# design.net
KiCad netlist of a schematic drawn in Altium Designer
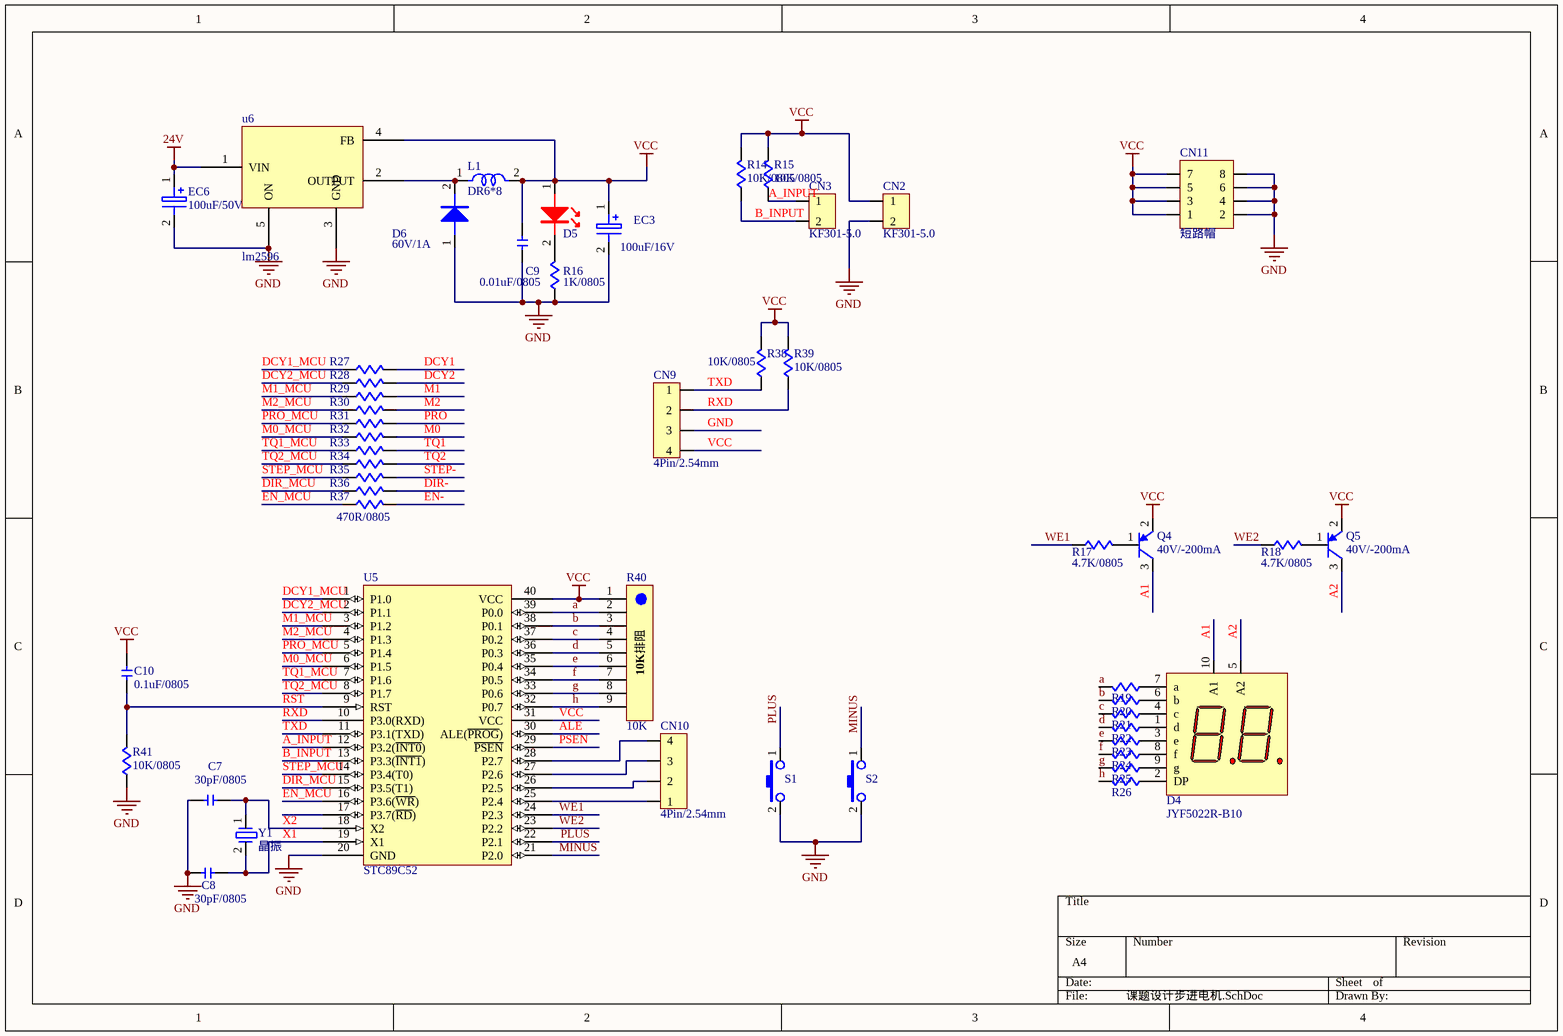
[diagram p0: 课题设计步进电机.SchDoc]

(export (version "E")
  (design (tool "Eeschema 10.0.6"))
  (components
    (comp (ref "C7")
      (value "30pF/0805")
      (footprint "WSC0805")
      (description "R21080010/工业C/消费C/贴片电容/30pF±5%/50V/NPO/0805")
      (libsource (lib "Capacitor_21") (part "R21080010"))
    )
    (comp (ref "C8")
      (value "30pF/0805")
      (footprint "WSC0805")
      (description "R21080010/工业C/消费C/贴片电容/30pF±5%/50V/NPO/0805")
      (libsource (lib "Capacitor_21") (part "R21080010"))
    )
    (comp (ref "C9")
      (value "0.01uF/0805")
      (footprint "WSC0805")
      (description "R21050097/工业C/消费C/贴片电容/0.01uF±5%/50V/NPO/0805")
      (libsource (lib "Capacitor_21") (part "R21050097"))
    )
    (comp (ref "C10")
      (value "0.1uF/0805")
      (footprint "WSC0805")
      (description "R21050005/工业B/消费B/贴片电容/0.1uF±10%/50V/X7R/0805")
      (libsource (lib "Capacitor_21") (part "R21050005"))
    )
    (comp (ref "CN2")
      (value "KF301-5.0")
      (footprint "KF301-5.0")
      (libsource (lib "Integrated_Library1") (part "KF301-5.0"))
    )
    (comp (ref "CN3")
      (value "KF301-5.0")
      (footprint "KF301-5.0")
      (libsource (lib "Integrated_Library1") (part "KF301-5.0"))
    )
    (comp (ref "CN9")
      (value "4Pin/2.54mm")
      (footprint "THT-CON4-2.54-2.54A/S-H8.5")
      (description "R30041122/消费B/普通插座/单排排母/4PIN/3A/单排/直脚/鱼叉母座/2.54mm/-40~105℃/H=8.5mm")
      (libsource (lib "Connector_30") (part "R30041122"))
    )
    (comp (ref "CN10")
      (value "4Pin/2.54mm")
      (footprint "THT-CON4-2.54-2.54A/S-H8.5")
      (description "R30041122/消费B/普通插座/单排排母/4PIN/3A/单排/直脚/鱼叉母座/2.54mm/-40~105℃/H=8.5mm")
      (libsource (lib "") (part "R30041122_1"))
    )
    (comp (ref "CN11")
      (value "短路帽")
      (footprint "THT-CON2*4-2.54-5.08A/D")
      (libsource (lib "temp") (part "2*54Pin/2.54mm"))
    )
    (comp (ref "D4")
      (value "JYF5022R-B10")
      (footprint "LED10-2.54*15.24-19A/S-AA")
      (description "R26010188/消费C/数码管/2位/共阳/红色630nm/40mcd/25*19*8mm/无铅")
      (libsource (lib "Semiconductor_26") (part "R26010188"))
    )
    (comp (ref "D5")
      (value "LED0805")
      (footprint "SD0805")
      (description "R26010108/工业A/消费A/发光二极管/红色/61mcd@20mA/0805SMD/LED0805")
      (libsource (lib "Semiconductor_26") (part "R26010108"))
    )
    (comp (ref "D6")
      (value "60V/1A")
      (footprint "SDO-214AC(SMA)")
      (description "R26030097/工业C/肖特基二极管/60V/1A/0.70V/SMA/B160")
      (libsource (lib "Semiconductor_26") (part "R26030097"))
    )
    (comp (ref "EC3")
      (value "100uF/16V")
      (footprint "CAPC2-5-5*11A/D")
      (description "R21010764/消费C/铝电解电容/105℃/100uF/16V/φ5*11")
      (libsource (lib "Capacitor_21") (part "R21010764"))
    )
    (comp (ref "EC6")
      (value "100uF/50V")
      (footprint "CAPC2-3.5-8*11.5A/S")
      (description "R21010695/消费C/电解电容/105℃/100uF/50v/φ8*11.5/引脚间距3.5mm")
      (libsource (lib "Capacitor_21") (part "R21010695"))
    )
    (comp (ref "L1")
      (value "DR6*8")
      (footprint "L2-3-8*11A/S")
      (description "R22011019/消费A/工字型电感DR6*8/100uH/MC1600-L3")
      (libsource (lib "Inductor_22") (part "R22011019"))
    )
    (comp (ref "Q4")
      (value "40V/-200mA")
      (footprint "WSOT-23")
      (description "R26080002/工业A/消费A/小信号三极管/PNP/-40V/-200mA/SOT-23")
      (libsource (lib "Semiconductor_26") (part "R26080002"))
    )
    (comp (ref "Q5")
      (value "40V/-200mA")
      (footprint "WSOT-23")
      (description "R26080002/工业A/消费A/小信号三极管/PNP/-40V/-200mA/SOT-23")
      (libsource (lib "Semiconductor_26") (part "R26080002"))
    )
    (comp (ref "R14")
      (value "10K/0805")
      (footprint "WSR0805")
      (description "R20180048/工业A/消费A/贴片电阻/1/8W/10KΩ±5%/0805")
      (libsource (lib "Resistor_20") (part "R20180048"))
    )
    (comp (ref "R15")
      (value "10K/0805")
      (footprint "WSR0805")
      (description "R20180048/工业A/消费A/贴片电阻/1/8W/10KΩ±5%/0805")
      (libsource (lib "Resistor_20") (part "R20180048"))
    )
    (comp (ref "R16")
      (value "1K/0805")
      (footprint "WSR0805")
      (description "R20180023/工业A/消费A/贴片电阻/1/8W/1KΩ±5%/0805")
      (libsource (lib "Resistor_20") (part "R20180023"))
    )
    (comp (ref "R17")
      (value "4.7K/0805")
      (footprint "WSR0805")
      (description "R20180039/工业A/消费A/贴片电阻/1/8W/4.7KΩ±5%/0805")
      (libsource (lib "Resistor_20") (part "R20180039"))
    )
    (comp (ref "R18")
      (value "4.7K/0805")
      (footprint "WSR0805")
      (description "R20180039/工业A/消费A/贴片电阻/1/8W/4.7KΩ±5%/0805")
      (libsource (lib "Resistor_20") (part "R20180039"))
    )
    (comp (ref "R19")
      (value "470R/0805")
      (footprint "WSR0805")
      (description "R20180017/工业A/消费A/贴片电阻/1/8W/470Ω±5%/0805")
      (libsource (lib "Resistor_20") (part "R20180017"))
    )
    (comp (ref "R20")
      (value "470R/0805")
      (footprint "WSR0805")
      (description "R20180017/工业A/消费A/贴片电阻/1/8W/470Ω±5%/0805")
      (libsource (lib "Resistor_20") (part "R20180017"))
    )
    (comp (ref "R21")
      (value "470R/0805")
      (footprint "WSR0805")
      (description "R20180017/工业A/消费A/贴片电阻/1/8W/470Ω±5%/0805")
      (libsource (lib "Resistor_20") (part "R20180017"))
    )
    (comp (ref "R22")
      (value "470R/0805")
      (footprint "WSR0805")
      (description "R20180017/工业A/消费A/贴片电阻/1/8W/470Ω±5%/0805")
      (libsource (lib "Resistor_20") (part "R20180017"))
    )
    (comp (ref "R23")
      (value "470R/0805")
      (footprint "WSR0805")
      (description "R20180017/工业A/消费A/贴片电阻/1/8W/470Ω±5%/0805")
      (libsource (lib "Resistor_20") (part "R20180017"))
    )
    (comp (ref "R24")
      (value "470R/0805")
      (footprint "WSR0805")
      (description "R20180017/工业A/消费A/贴片电阻/1/8W/470Ω±5%/0805")
      (libsource (lib "Resistor_20") (part "R20180017"))
    )
    (comp (ref "R25")
      (value "470R/0805")
      (footprint "WSR0805")
      (description "R20180017/工业A/消费A/贴片电阻/1/8W/470Ω±5%/0805")
      (libsource (lib "Resistor_20") (part "R20180017"))
    )
    (comp (ref "R26")
      (value "470R/0805")
      (footprint "WSR0805")
      (description "R20180017/工业A/消费A/贴片电阻/1/8W/470Ω±5%/0805")
      (libsource (lib "Resistor_20") (part "R20180017"))
    )
    (comp (ref "R27")
      (value "470R/0805")
      (footprint "WSR0805")
      (description "R20180245/工业C/消费C/贴片电阻/1/8W/470Ω±1%/0805/ROHS")
      (libsource (lib "Resistor_20") (part "R20180245"))
    )
    (comp (ref "R28")
      (value "470R/0805")
      (footprint "WSR0805")
      (description "R20180245/工业C/消费C/贴片电阻/1/8W/470Ω±1%/0805/ROHS")
      (libsource (lib "Resistor_20") (part "R20180245"))
    )
    (comp (ref "R29")
      (value "470R/0805")
      (footprint "WSR0805")
      (description "R20180245/工业C/消费C/贴片电阻/1/8W/470Ω±1%/0805/ROHS")
      (libsource (lib "Resistor_20") (part "R20180245"))
    )
    (comp (ref "R30")
      (value "470R/0805")
      (footprint "WSR0805")
      (description "R20180245/工业C/消费C/贴片电阻/1/8W/470Ω±1%/0805/ROHS")
      (libsource (lib "Resistor_20") (part "R20180245"))
    )
    (comp (ref "R31")
      (value "470R/0805")
      (footprint "WSR0805")
      (description "R20180245/工业C/消费C/贴片电阻/1/8W/470Ω±1%/0805/ROHS")
      (libsource (lib "Resistor_20") (part "R20180245"))
    )
    (comp (ref "R32")
      (value "470R/0805")
      (footprint "WSR0805")
      (description "R20180245/工业C/消费C/贴片电阻/1/8W/470Ω±1%/0805/ROHS")
      (libsource (lib "Resistor_20") (part "R20180245"))
    )
    (comp (ref "R33")
      (value "470R/0805")
      (footprint "WSR0805")
      (description "R20180245/工业C/消费C/贴片电阻/1/8W/470Ω±1%/0805/ROHS")
      (libsource (lib "Resistor_20") (part "R20180245"))
    )
    (comp (ref "R34")
      (value "470R/0805")
      (footprint "WSR0805")
      (description "R20180245/工业C/消费C/贴片电阻/1/8W/470Ω±1%/0805/ROHS")
      (libsource (lib "Resistor_20") (part "R20180245"))
    )
    (comp (ref "R35")
      (value "470R/0805")
      (footprint "WSR0805")
      (description "R20180245/工业C/消费C/贴片电阻/1/8W/470Ω±1%/0805/ROHS")
      (libsource (lib "Resistor_20") (part "R20180245"))
    )
    (comp (ref "R36")
      (value "470R/0805")
      (footprint "WSR0805")
      (description "R20180245/工业C/消费C/贴片电阻/1/8W/470Ω±1%/0805/ROHS")
      (libsource (lib "Resistor_20") (part "R20180245"))
    )
    (comp (ref "R37")
      (value "470R/0805")
      (footprint "WSR0805")
      (description "R20180245/工业C/消费C/贴片电阻/1/8W/470Ω±1%/0805/ROHS")
      (libsource (lib "Resistor_20") (part "R20180245"))
    )
    (comp (ref "R38")
      (value "10K/0805")
      (footprint "WSR0805")
      (description "R20180048/工业A/消费A/贴片电阻/1/8W/10KΩ±5%/0805")
      (libsource (lib "Resistor_20") (part "R20180048"))
    )
    (comp (ref "R39")
      (value "10K/0805")
      (footprint "WSR0805")
      (description "R20180048/工业A/消费A/贴片电阻/1/8W/10KΩ±5%/0805")
      (libsource (lib "Resistor_20") (part "R20180048"))
    )
    (comp (ref "R40") (value "10K") (footprint "R_9*2.54") (libsource (lib "lib of tj") (part "插件排阻")))
    (comp (ref "R41")
      (value "10K/0805")
      (footprint "WSR0805")
      (description "R20180048/工业A/消费A/贴片电阻/1/8W/10KΩ±5%/0805")
      (libsource (lib "Resistor_20") (part "R20180048"))
    )
    (comp (ref "S1")
      (value "12VDC/30mA")
      (footprint "THT-SW4-6.5*4.5A/D")
      (description "R34010007/消费A/微动开关/12VDC/30mA/6*6*4.3mm/插件")
      (libsource (lib "Low-tension_34") (part "R34010007"))
    )
    (comp (ref "S2")
      (value "12VDC/30mA")
      (footprint "THT-SW4-6.5*4.5A/D")
      (description "R34010007/消费A/微动开关/12VDC/30mA/6*6*4.3mm/插件")
      (libsource (lib "Low-tension_34") (part "R34010007"))
    )
    (comp (ref "U5")
      (value "STC89C52")
      (footprint "DIP-40")
      (libsource (lib "Integrated_Library1") (part "AT89C51"))
    )
    (comp (ref "u6")
      (value "lm2596")
      (footprint "TO-220-5L")
      (libsource (lib "Integrated_Library1") (part "lm2596"))
    )
    (comp (ref "Y1") (value "晶振") (footprint "HC-49") (libsource (lib "temp") (part "晶振")))
  )
  (nets
    (net (code "1") (name "/A1") (class "Default")
      (node (ref "D4") (pin "10") (pinfunction "A1_10") (pintype "passive"))
      (node (ref "Q4") (pin "3") (pinfunction "C_3") (pintype "passive"))
    )
    (net (code "2") (name "/A2") (class "Default")
      (node (ref "D4") (pin "5") (pinfunction "A2_5") (pintype "passive"))
      (node (ref "Q5") (pin "3") (pinfunction "C_3") (pintype "passive"))
    )
    (net (code "3") (name "/ALE") (class "Default")
      (node (ref "U5") (pin "30") (pinfunction "ALE(~{PROG})_30") (pintype "bidirectional"))
    )
    (net (code "4") (name "/A_INPUT") (class "Default")
      (node (ref "CN3") (pin "1") (pinfunction "1_1") (pintype "passive"))
      (node (ref "R15") (pin "1") (pinfunction "1_1") (pintype "passive"))
      (node (ref "U5") (pin "12") (pinfunction "P3.2(~{INT0})_12") (pintype "bidirectional"))
    )
    (net (code "5") (name "/B_INPUT") (class "Default")
      (node (ref "CN3") (pin "2") (pinfunction "2_2") (pintype "passive"))
      (node (ref "R14") (pin "1") (pinfunction "1_1") (pintype "passive"))
      (node (ref "U5") (pin "13") (pinfunction "P3.3(~{INT1})_13") (pintype "bidirectional"))
    )
    (net (code "6") (name "/DCY1") (class "Default")
      (node (ref "R27") (pin "2") (pinfunction "2_2") (pintype "passive"))
    )
    (net (code "7") (name "/DCY1_MCU") (class "Default")
      (node (ref "R27") (pin "1") (pinfunction "1_1") (pintype "passive"))
      (node (ref "U5") (pin "1") (pinfunction "P1.0_1") (pintype "bidirectional"))
    )
    (net (code "8") (name "/DCY2") (class "Default")
      (node (ref "R28") (pin "2") (pinfunction "2_2") (pintype "passive"))
    )
    (net (code "9") (name "/DCY2_MCU") (class "Default")
      (node (ref "R28") (pin "1") (pinfunction "1_1") (pintype "passive"))
      (node (ref "U5") (pin "2") (pinfunction "P1.1_2") (pintype "bidirectional"))
    )
    (net (code "10") (name "/DIR-") (class "Default")
      (node (ref "R36") (pin "2") (pinfunction "2_2") (pintype "passive"))
    )
    (net (code "11") (name "/DIR_MCU") (class "Default")
      (node (ref "R36") (pin "1") (pinfunction "1_1") (pintype "passive"))
      (node (ref "U5") (pin "15") (pinfunction "P3.5(T1)_15") (pintype "bidirectional"))
    )
    (net (code "12") (name "/EN-") (class "Default")
      (node (ref "R37") (pin "2") (pinfunction "2_2") (pintype "passive"))
    )
    (net (code "13") (name "/EN_MCU") (class "Default")
      (node (ref "R37") (pin "1") (pinfunction "1_1") (pintype "passive"))
      (node (ref "U5") (pin "16") (pinfunction "P3.6(~{WR})_16") (pintype "bidirectional"))
    )
    (net (code "14") (name "/M0") (class "Default")
      (node (ref "R32") (pin "2") (pinfunction "2_2") (pintype "passive"))
    )
    (net (code "15") (name "/M0_MCU") (class "Default")
      (node (ref "R32") (pin "1") (pinfunction "1_1") (pintype "passive"))
      (node (ref "U5") (pin "6") (pinfunction "P1.5_6") (pintype "bidirectional"))
    )
    (net (code "16") (name "/M1") (class "Default")
      (node (ref "R29") (pin "2") (pinfunction "2_2") (pintype "passive"))
    )
    (net (code "17") (name "/M1_MCU") (class "Default")
      (node (ref "R29") (pin "1") (pinfunction "1_1") (pintype "passive"))
      (node (ref "U5") (pin "3") (pinfunction "P1.2_3") (pintype "bidirectional"))
    )
    (net (code "18") (name "/M2") (class "Default")
      (node (ref "R30") (pin "2") (pinfunction "2_2") (pintype "passive"))
    )
    (net (code "19") (name "/M2_MCU") (class "Default")
      (node (ref "R30") (pin "1") (pinfunction "1_1") (pintype "passive"))
      (node (ref "U5") (pin "4") (pinfunction "P1.3_4") (pintype "bidirectional"))
    )
    (net (code "20") (name "/MINUS") (class "Default")
      (node (ref "S2") (pin "1") (pinfunction "1_1") (pintype "passive"))
      (node (ref "U5") (pin "21") (pinfunction "P2.0_21") (pintype "bidirectional"))
    )
    (net (code "21") (name "/PLUS") (class "Default")
      (node (ref "S1") (pin "1") (pinfunction "1_1") (pintype "passive"))
      (node (ref "U5") (pin "22") (pinfunction "P2.1_22") (pintype "bidirectional"))
    )
    (net (code "22") (name "/PRO") (class "Default")
      (node (ref "R31") (pin "2") (pinfunction "2_2") (pintype "passive"))
    )
    (net (code "23") (name "/PRO_MCU") (class "Default")
      (node (ref "R31") (pin "1") (pinfunction "1_1") (pintype "passive"))
      (node (ref "U5") (pin "5") (pinfunction "P1.4_5") (pintype "bidirectional"))
    )
    (net (code "24") (name "/PSEN") (class "Default")
      (node (ref "U5") (pin "29") (pinfunction "~{PSEN}_29") (pintype "bidirectional"))
    )
    (net (code "25") (name "/RST") (class "Default")
      (node (ref "C10") (pin "1") (pinfunction "1_1") (pintype "passive"))
      (node (ref "R41") (pin "2") (pinfunction "2_2") (pintype "passive"))
      (node (ref "U5") (pin "9") (pinfunction "RST_9") (pintype "input"))
    )
    (net (code "26") (name "/RXD") (class "Default")
      (node (ref "CN9") (pin "2") (pinfunction "2_2") (pintype "passive"))
      (node (ref "R39") (pin "1") (pinfunction "1_1") (pintype "passive"))
      (node (ref "U5") (pin "10") (pinfunction "P3.0(RXD)_10") (pintype "passive"))
    )
    (net (code "27") (name "/STEP-") (class "Default")
      (node (ref "R35") (pin "2") (pinfunction "2_2") (pintype "passive"))
    )
    (net (code "28") (name "/STEP_MCU") (class "Default")
      (node (ref "R35") (pin "1") (pinfunction "1_1") (pintype "passive"))
      (node (ref "U5") (pin "14") (pinfunction "P3.4(T0)_14") (pintype "bidirectional"))
    )
    (net (code "29") (name "/TQ1") (class "Default")
      (node (ref "R33") (pin "2") (pinfunction "2_2") (pintype "passive"))
    )
    (net (code "30") (name "/TQ1_MCU") (class "Default")
      (node (ref "R33") (pin "1") (pinfunction "1_1") (pintype "passive"))
      (node (ref "U5") (pin "7") (pinfunction "P1.6_7") (pintype "bidirectional"))
    )
    (net (code "31") (name "/TQ2") (class "Default")
      (node (ref "R34") (pin "2") (pinfunction "2_2") (pintype "passive"))
    )
    (net (code "32") (name "/TQ2_MCU") (class "Default")
      (node (ref "R34") (pin "1") (pinfunction "1_1") (pintype "passive"))
      (node (ref "U5") (pin "8") (pinfunction "P1.7_8") (pintype "bidirectional"))
    )
    (net (code "33") (name "/TXD") (class "Default")
      (node (ref "CN9") (pin "1") (pinfunction "1_1") (pintype "passive"))
      (node (ref "R38") (pin "1") (pinfunction "1_1") (pintype "passive"))
      (node (ref "U5") (pin "11") (pinfunction "P3.1(TXD)_11") (pintype "bidirectional"))
    )
    (net (code "34") (name "/WE1") (class "Default")
      (node (ref "R17") (pin "1") (pinfunction "1_1") (pintype "passive"))
      (node (ref "U5") (pin "24") (pinfunction "P2.3_24") (pintype "bidirectional"))
    )
    (net (code "35") (name "/WE2") (class "Default")
      (node (ref "R18") (pin "1") (pinfunction "1_1") (pintype "passive"))
      (node (ref "U5") (pin "23") (pinfunction "P2.2_23") (pintype "bidirectional"))
    )
    (net (code "36") (name "/X1") (class "Default")
      (node (ref "C8") (pin "2") (pinfunction "2_2") (pintype "passive"))
      (node (ref "U5") (pin "19") (pinfunction "X1_19") (pintype "input"))
      (node (ref "Y1") (pin "2") (pinfunction "2_2") (pintype "passive"))
    )
    (net (code "37") (name "/X2") (class "Default")
      (node (ref "C7") (pin "2") (pinfunction "2_2") (pintype "passive"))
      (node (ref "U5") (pin "18") (pinfunction "X2_18") (pintype "input"))
      (node (ref "Y1") (pin "1") (pinfunction "1_1") (pintype "passive"))
    )
    (net (code "38") (name "/a") (class "Default")
      (node (ref "R19") (pin "2") (pinfunction "2_2") (pintype "passive"))
      (node (ref "R40") (pin "2") (pinfunction "2_2") (pintype "passive"))
      (node (ref "U5") (pin "39") (pinfunction "P0.0_39") (pintype "bidirectional"))
    )
    (net (code "39") (name "/b") (class "Default")
      (node (ref "R20") (pin "2") (pinfunction "2_2") (pintype "passive"))
      (node (ref "R40") (pin "3") (pinfunction "3_3") (pintype "passive"))
      (node (ref "U5") (pin "38") (pinfunction "P0.1_38") (pintype "bidirectional"))
    )
    (net (code "40") (name "/c") (class "Default")
      (node (ref "R21") (pin "2") (pinfunction "2_2") (pintype "passive"))
      (node (ref "R40") (pin "4") (pinfunction "4_4") (pintype "passive"))
      (node (ref "U5") (pin "37") (pinfunction "P0.2_37") (pintype "bidirectional"))
    )
    (net (code "41") (name "/d") (class "Default")
      (node (ref "R22") (pin "2") (pinfunction "2_2") (pintype "passive"))
      (node (ref "R40") (pin "5") (pinfunction "5_5") (pintype "passive"))
      (node (ref "U5") (pin "36") (pinfunction "P0.3_36") (pintype "bidirectional"))
    )
    (net (code "42") (name "/e") (class "Default")
      (node (ref "R23") (pin "2") (pinfunction "2_2") (pintype "passive"))
      (node (ref "R40") (pin "6") (pinfunction "6_6") (pintype "passive"))
      (node (ref "U5") (pin "35") (pinfunction "P0.4_35") (pintype "bidirectional"))
    )
    (net (code "43") (name "/f") (class "Default")
      (node (ref "R24") (pin "2") (pinfunction "2_2") (pintype "passive"))
      (node (ref "R40") (pin "7") (pinfunction "7_7") (pintype "passive"))
      (node (ref "U5") (pin "34") (pinfunction "P0.5_34") (pintype "bidirectional"))
    )
    (net (code "44") (name "/g") (class "Default")
      (node (ref "R25") (pin "2") (pinfunction "2_2") (pintype "passive"))
      (node (ref "R40") (pin "8") (pinfunction "8_8") (pintype "passive"))
      (node (ref "U5") (pin "33") (pinfunction "P0.6_33") (pintype "bidirectional"))
    )
    (net (code "45") (name "/h") (class "Default")
      (node (ref "R26") (pin "2") (pinfunction "2_2") (pintype "passive"))
      (node (ref "R40") (pin "9") (pinfunction "9_9") (pintype "passive"))
      (node (ref "U5") (pin "32") (pinfunction "P0.7_32") (pintype "bidirectional"))
    )
    (net (code "46") (name "24V") (class "Default")
      (node (ref "EC6") (pin "1") (pinfunction "1_1") (pintype "passive"))
      (node (ref "u6") (pin "1") (pinfunction "VIN_1") (pintype "passive"))
    )
    (net (code "47") (name "GND") (class "Default")
      (node (ref "C7") (pin "1") (pinfunction "1_1") (pintype "passive"))
      (node (ref "C8") (pin "1") (pinfunction "1_1") (pintype "passive"))
      (node (ref "C9") (pin "1") (pinfunction "1_1") (pintype "passive"))
      (node (ref "CN11") (pin "2") (pinfunction "2_2") (pintype "passive"))
      (node (ref "CN11") (pin "4") (pinfunction "4_4") (pintype "passive"))
      (node (ref "CN11") (pin "6") (pinfunction "6_6") (pintype "passive"))
      (node (ref "CN11") (pin "8") (pinfunction "8_8") (pintype "passive"))
      (node (ref "CN2") (pin "2") (pinfunction "2_2") (pintype "passive"))
      (node (ref "CN9") (pin "3") (pinfunction "3_3") (pintype "passive"))
      (node (ref "D6") (pin "1") (pinfunction "A_1") (pintype "passive"))
      (node (ref "EC3") (pin "2") (pinfunction "2_2") (pintype "passive"))
      (node (ref "EC6") (pin "2") (pinfunction "2_2") (pintype "passive"))
      (node (ref "R16") (pin "1") (pinfunction "1_1") (pintype "passive"))
      (node (ref "R41") (pin "1") (pinfunction "1_1") (pintype "passive"))
      (node (ref "S1") (pin "2") (pinfunction "2_2") (pintype "passive"))
      (node (ref "S2") (pin "2") (pinfunction "2_2") (pintype "passive"))
      (node (ref "U5") (pin "20") (pinfunction "GND_20") (pintype "passive"))
      (node (ref "u6") (pin "3") (pinfunction "GND_3") (pintype "passive"))
      (node (ref "u6") (pin "5") (pinfunction "ON_5") (pintype "passive"))
    )
    (net (code "48") (name "Net-(D4-DP)") (class "Default")
      (node (ref "D4") (pin "2") (pinfunction "DP_2") (pintype "passive"))
      (node (ref "R26") (pin "1") (pinfunction "1_1") (pintype "passive"))
    )
    (net (code "49") (name "Net-(D4-a)") (class "Default")
      (node (ref "D4") (pin "7") (pinfunction "a_7") (pintype "passive"))
      (node (ref "R19") (pin "1") (pinfunction "1_1") (pintype "passive"))
    )
    (net (code "50") (name "Net-(D4-b)") (class "Default")
      (node (ref "D4") (pin "6") (pinfunction "b_6") (pintype "passive"))
      (node (ref "R20") (pin "1") (pinfunction "1_1") (pintype "passive"))
    )
    (net (code "51") (name "Net-(D4-c)") (class "Default")
      (node (ref "D4") (pin "4") (pinfunction "c_4") (pintype "passive"))
      (node (ref "R21") (pin "1") (pinfunction "1_1") (pintype "passive"))
    )
    (net (code "52") (name "Net-(D4-d)") (class "Default")
      (node (ref "D4") (pin "1") (pinfunction "d_1") (pintype "passive"))
      (node (ref "R22") (pin "1") (pinfunction "1_1") (pintype "passive"))
    )
    (net (code "53") (name "Net-(D4-e)") (class "Default")
      (node (ref "D4") (pin "3") (pinfunction "e_3") (pintype "passive"))
      (node (ref "R23") (pin "1") (pinfunction "1_1") (pintype "passive"))
    )
    (net (code "54") (name "Net-(D4-f)") (class "Default")
      (node (ref "D4") (pin "8") (pinfunction "f_8") (pintype "passive"))
      (node (ref "R24") (pin "1") (pinfunction "1_1") (pintype "passive"))
    )
    (net (code "55") (name "Net-(D4-g)") (class "Default")
      (node (ref "D4") (pin "9") (pinfunction "g_9") (pintype "passive"))
      (node (ref "R25") (pin "1") (pinfunction "1_1") (pintype "passive"))
    )
    (net (code "56") (name "Net-(D5-K)") (class "Default")
      (node (ref "D5") (pin "2") (pinfunction "K_2") (pintype "passive"))
      (node (ref "R16") (pin "2") (pinfunction "2_2") (pintype "passive"))
    )
    (net (code "57") (name "Net-(D6-K)") (class "Default")
      (node (ref "D6") (pin "2") (pinfunction "K_2") (pintype "passive"))
      (node (ref "L1") (pin "1") (pinfunction "1_1") (pintype "passive"))
      (node (ref "u6") (pin "2") (pinfunction "OUTPUT_2") (pintype "passive"))
    )
    (net (code "58") (name "Net-(Q4-B)") (class "Default")
      (node (ref "Q4") (pin "1") (pinfunction "B_1") (pintype "passive"))
      (node (ref "R17") (pin "2") (pinfunction "2_2") (pintype "passive"))
    )
    (net (code "59") (name "Net-(Q5-B)") (class "Default")
      (node (ref "Q5") (pin "1") (pinfunction "B_1") (pintype "passive"))
      (node (ref "R18") (pin "2") (pinfunction "2_2") (pintype "passive"))
    )
    (net (code "60") (name "Net-(U5-P2.4)") (class "Default")
      (node (ref "CN10") (pin "1") (pinfunction "1_1") (pintype "passive"))
      (node (ref "U5") (pin "25") (pinfunction "P2.4_25") (pintype "bidirectional"))
    )
    (net (code "61") (name "Net-(U5-P2.5)") (class "Default")
      (node (ref "CN10") (pin "2") (pinfunction "2_2") (pintype "passive"))
      (node (ref "U5") (pin "26") (pinfunction "P2.5_26") (pintype "bidirectional"))
    )
    (net (code "62") (name "Net-(U5-P2.6)") (class "Default")
      (node (ref "CN10") (pin "3") (pinfunction "3_3") (pintype "passive"))
      (node (ref "U5") (pin "27") (pinfunction "P2.6_27") (pintype "bidirectional"))
    )
    (net (code "63") (name "Net-(U5-P2.7)") (class "Default")
      (node (ref "CN10") (pin "4") (pinfunction "4_4") (pintype "passive"))
      (node (ref "U5") (pin "28") (pinfunction "P2.7_28") (pintype "bidirectional"))
    )
    (net (code "64") (name "VCC") (class "Default")
      (node (ref "C10") (pin "2") (pinfunction "2_2") (pintype "passive"))
      (node (ref "C9") (pin "2") (pinfunction "2_2") (pintype "passive"))
      (node (ref "CN11") (pin "1") (pinfunction "1_1") (pintype "passive"))
      (node (ref "CN11") (pin "3") (pinfunction "3_3") (pintype "passive"))
      (node (ref "CN11") (pin "5") (pinfunction "5_5") (pintype "passive"))
      (node (ref "CN11") (pin "7") (pinfunction "7_7") (pintype "passive"))
      (node (ref "CN2") (pin "1") (pinfunction "1_1") (pintype "passive"))
      (node (ref "CN9") (pin "4") (pinfunction "4_4") (pintype "passive"))
      (node (ref "D5") (pin "1") (pinfunction "A_1") (pintype "passive"))
      (node (ref "EC3") (pin "1") (pinfunction "1_1") (pintype "passive"))
      (node (ref "L1") (pin "2") (pinfunction "2_2") (pintype "passive"))
      (node (ref "Q4") (pin "2") (pinfunction "E_2") (pintype "passive"))
      (node (ref "Q5") (pin "2") (pinfunction "E_2") (pintype "passive"))
      (node (ref "R14") (pin "2") (pinfunction "2_2") (pintype "passive"))
      (node (ref "R15") (pin "2") (pinfunction "2_2") (pintype "passive"))
      (node (ref "R38") (pin "2") (pinfunction "2_2") (pintype "passive"))
      (node (ref "R39") (pin "2") (pinfunction "2_2") (pintype "passive"))
      (node (ref "R40") (pin "1") (pinfunction "COM_1") (pintype "passive"))
      (node (ref "U5") (pin "31") (pinfunction "VCC_31") (pintype "power_in"))
      (node (ref "U5") (pin "40") (pinfunction "VCC_40") (pintype "power_in"))
      (node (ref "u6") (pin "4") (pinfunction "FB_4") (pintype "passive"))
    )
    (net (code "65") (name "unconnected-(U5-P3.7(~{RD})-Pad17)") (class "Default")
      (node (ref "U5") (pin "17") (pinfunction "P3.7(~{RD})_17") (pintype "bidirectional"))
    )
  )
)
